# SUBBOARD-voltage_sensors.net
KiCad netlist of a schematic drawn in Altium Designer
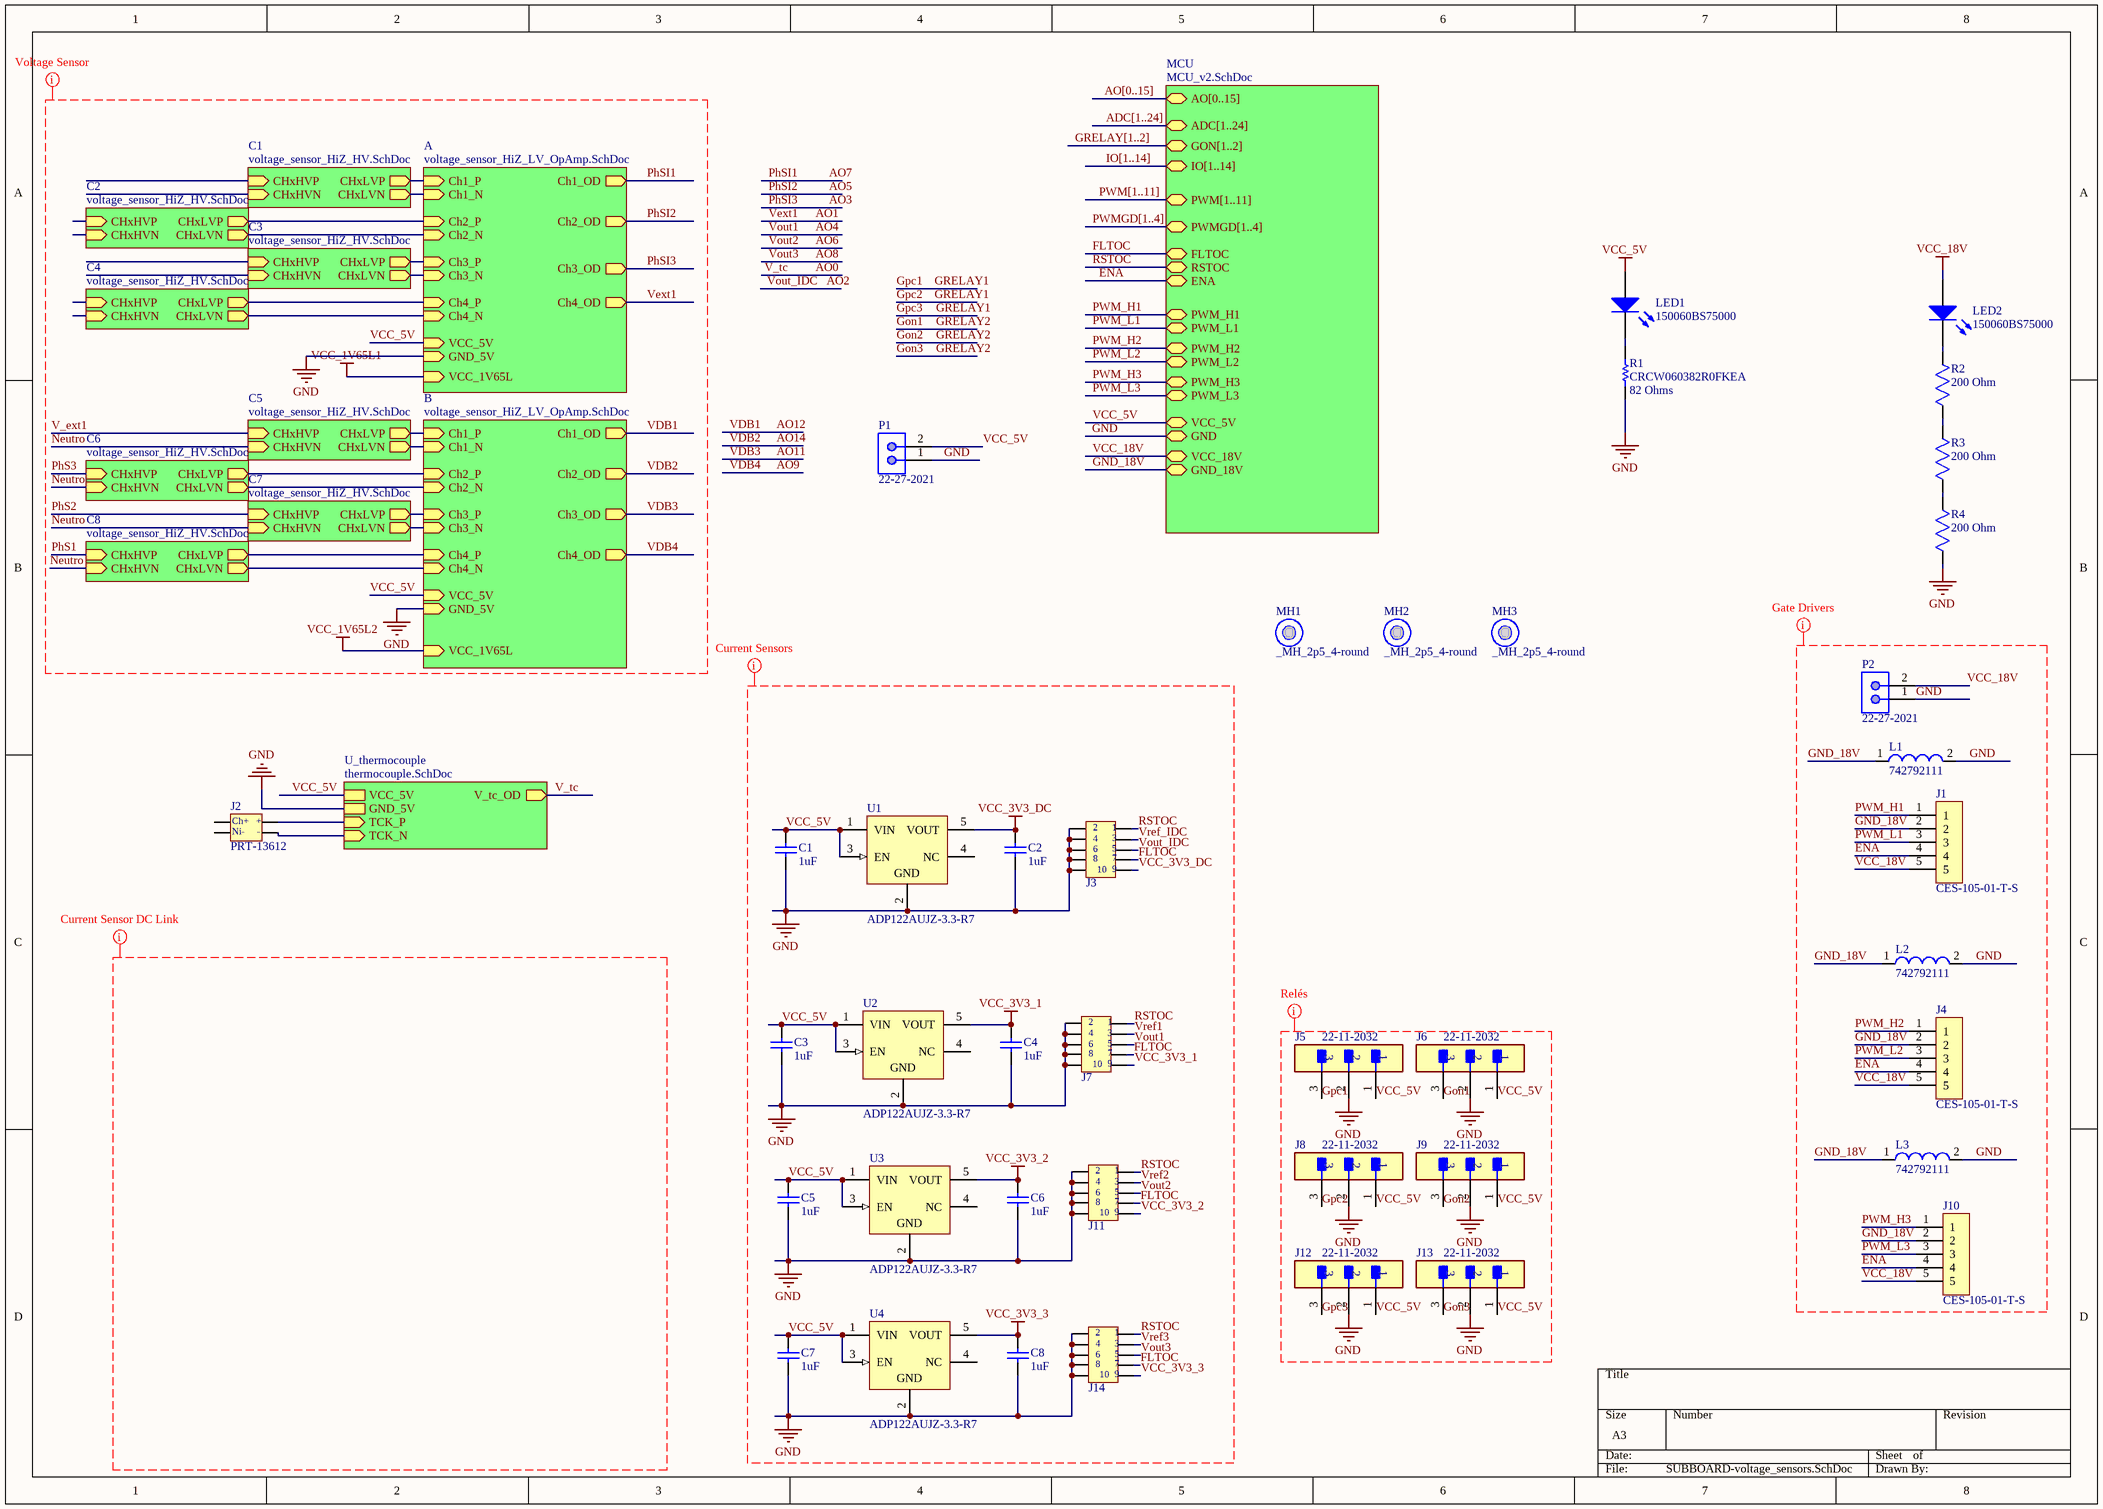
[diagram p0: SUBBOARD-voltage_sensors.SchDoc]

(export (version "E")
  (design (tool "Eeschema 10.0.6"))
  (components
    (comp (ref "C1")
      (value "1uF")
      (footprint "CAPC0603(1608)100_N")
      (description "CAP 1uF 50V ±20% 0603 (1608 Metric) Thickness 1mm SMD")
      (fields (field (name "TOLERANCE") "Â±20%") (field (name "Comment") "CAP 1uF 50V 0603(1608)"))
      (libsource (lib "Altium Content Vault") (part "CAP"))
    )
    (comp (ref "C2")
      (value "1uF")
      (footprint "CAPC0603(1608)100_N")
      (description "CAP 1uF 50V ±20% 0603 (1608 Metric) Thickness 1mm SMD")
      (fields (field (name "TOLERANCE") "Â±20%") (field (name "Comment") "CAP 1uF 50V 0603(1608)"))
      (libsource (lib "Altium Content Vault") (part "CAP"))
    )
    (comp (ref "C3")
      (value "1uF")
      (footprint "CAPC0603(1608)100_N")
      (description "CAP 1uF 50V ±20% 0603 (1608 Metric) Thickness 1mm SMD")
      (fields (field (name "TOLERANCE") "Â±20%") (field (name "Comment") "CAP 1uF 50V 0603(1608)"))
      (libsource (lib "Altium Content Vault") (part "CAP"))
    )
    (comp (ref "C4")
      (value "1uF")
      (footprint "CAPC0603(1608)100_N")
      (description "CAP 1uF 50V ±20% 0603 (1608 Metric) Thickness 1mm SMD")
      (fields (field (name "TOLERANCE") "Â±20%") (field (name "Comment") "CAP 1uF 50V 0603(1608)"))
      (libsource (lib "Altium Content Vault") (part "CAP"))
    )
    (comp (ref "C5")
      (value "1uF")
      (footprint "CAPC0603(1608)100_N")
      (description "CAP 1uF 50V ±20% 0603 (1608 Metric) Thickness 1mm SMD")
      (fields (field (name "TOLERANCE") "Â±20%") (field (name "Comment") "CAP 1uF 50V 0603(1608)"))
      (libsource (lib "Altium Content Vault") (part "CAP"))
    )
    (comp (ref "C6")
      (value "1uF")
      (footprint "CAPC0603(1608)100_N")
      (description "CAP 1uF 50V ±20% 0603 (1608 Metric) Thickness 1mm SMD")
      (fields (field (name "TOLERANCE") "Â±20%") (field (name "Comment") "CAP 1uF 50V 0603(1608)"))
      (libsource (lib "Altium Content Vault") (part "CAP"))
    )
    (comp (ref "C7")
      (value "1uF")
      (footprint "CAPC0603(1608)100_N")
      (description "CAP 1uF 50V ±20% 0603 (1608 Metric) Thickness 1mm SMD")
      (fields (field (name "TOLERANCE") "Â±20%") (field (name "Comment") "CAP 1uF 50V 0603(1608)"))
      (libsource (lib "Altium Content Vault") (part "CAP"))
    )
    (comp (ref "C8")
      (value "1uF")
      (footprint "CAPC0603(1608)100_N")
      (description "CAP 1uF 50V ±20% 0603 (1608 Metric) Thickness 1mm SMD")
      (fields (field (name "TOLERANCE") "Â±20%") (field (name "Comment") "CAP 1uF 50V 0603(1608)"))
      (libsource (lib "Altium Content Vault") (part "CAP"))
    )
    (comp (ref "J1")
      (value "CES-105-01-T-S")
      (footprint "CES-105-01-T-S")
      (fields (field (name "MANUFACTURER") "Samtec"))
      (libsource (lib "Altium_Library_POWERLAB") (part "CES-105-01-T-S"))
    )
    (comp (ref "J2")
      (value "PRT-13612")
      (footprint "PRT-13612")
      (description "THERMOCOUPLE CONN - PCC-SMP-K")
      (fields (field (name "MANUFACTURER") "SparkFun"))
      (libsource (lib "Altium_Library_POWERLAB") (part "PRT-13612"))
    )
    (comp (ref "J3")
      (value "0878311020")
      (footprint "0878311020")
      (description "Conn Shrouded Header HDR 10 POS 2mm Solder ST Thru-Hole Milli-Grid™ Tube")
      (fields (field (name "MANUFACTURER") "Molex"))
      (libsource (lib "Altium_Library_POWERLAB") (part "0878311020"))
    )
    (comp (ref "J4")
      (value "CES-105-01-T-S")
      (footprint "CES-105-01-T-S")
      (fields (field (name "MANUFACTURER") "Samtec"))
      (libsource (lib "Altium_Library_POWERLAB") (part "CES-105-01-T-S"))
    )
    (comp (ref "J5")
      (value "22-11-2032")
      (footprint "FP-22-11-2032-MFG")
      (description "CONN HEADER VERT 3POS 2.54MM")
      (fields
        (field (name "MANUFACTURER") "Molex")
        (field (name "OCTOPART") "https://octopart.com/22-11-2032-molex-10085")
      )
      (libsource (lib "Altium Content Vault") (part "0d3f023dd272f625e17a2be33dea85f"))
    )
    (comp (ref "J6")
      (value "22-11-2032")
      (footprint "FP-22-11-2032-MFG")
      (description "CONN HEADER VERT 3POS 2.54MM")
      (fields
        (field (name "MANUFACTURER") "Molex")
        (field (name "OCTOPART") "https://octopart.com/22-11-2032-molex-10085")
      )
      (libsource (lib "Altium Content Vault") (part "0d3f023dd272f625e17a2be33dea85f"))
    )
    (comp (ref "J7")
      (value "0878311020")
      (footprint "0878311020")
      (description "Conn Shrouded Header HDR 10 POS 2mm Solder ST Thru-Hole Milli-Grid™ Tube")
      (fields (field (name "MANUFACTURER") "Molex"))
      (libsource (lib "Altium_Library_POWERLAB") (part "0878311020"))
    )
    (comp (ref "J8")
      (value "22-11-2032")
      (footprint "FP-22-11-2032-MFG")
      (description "CONN HEADER VERT 3POS 2.54MM")
      (fields
        (field (name "MANUFACTURER") "Molex")
        (field (name "OCTOPART") "https://octopart.com/22-11-2032-molex-10085")
      )
      (libsource (lib "Altium Content Vault") (part "0d3f023dd272f625e17a2be33dea85f"))
    )
    (comp (ref "J9")
      (value "22-11-2032")
      (footprint "FP-22-11-2032-MFG")
      (description "CONN HEADER VERT 3POS 2.54MM")
      (fields
        (field (name "MANUFACTURER") "Molex")
        (field (name "OCTOPART") "https://octopart.com/22-11-2032-molex-10085")
      )
      (libsource (lib "Altium Content Vault") (part "0d3f023dd272f625e17a2be33dea85f"))
    )
    (comp (ref "J10")
      (value "CES-105-01-T-S")
      (footprint "CES-105-01-T-S")
      (fields (field (name "MANUFACTURER") "Samtec"))
      (libsource (lib "Altium_Library_POWERLAB") (part "CES-105-01-T-S"))
    )
    (comp (ref "J11")
      (value "0878311020")
      (footprint "0878311020")
      (description "Conn Shrouded Header HDR 10 POS 2mm Solder ST Thru-Hole Milli-Grid™ Tube")
      (fields (field (name "MANUFACTURER") "Molex"))
      (libsource (lib "Altium_Library_POWERLAB") (part "0878311020"))
    )
    (comp (ref "J12")
      (value "22-11-2032")
      (footprint "FP-22-11-2032-MFG")
      (description "CONN HEADER VERT 3POS 2.54MM")
      (fields
        (field (name "MANUFACTURER") "Molex")
        (field (name "OCTOPART") "https://octopart.com/22-11-2032-molex-10085")
      )
      (libsource (lib "Altium Content Vault") (part "0d3f023dd272f625e17a2be33dea85f"))
    )
    (comp (ref "J13")
      (value "22-11-2032")
      (footprint "FP-22-11-2032-MFG")
      (description "CONN HEADER VERT 3POS 2.54MM")
      (fields
        (field (name "MANUFACTURER") "Molex")
        (field (name "OCTOPART") "https://octopart.com/22-11-2032-molex-10085")
      )
      (libsource (lib "Altium Content Vault") (part "0d3f023dd272f625e17a2be33dea85f"))
    )
    (comp (ref "J14")
      (value "0878311020")
      (footprint "0878311020")
      (description "Conn Shrouded Header HDR 10 POS 2mm Solder ST Thru-Hole Milli-Grid™ Tube")
      (fields (field (name "MANUFACTURER") "Molex"))
      (libsource (lib "Altium_Library_POWERLAB") (part "0878311020"))
    )
    (comp (ref "L1")
      (value "742792111")
      (footprint "SMD-1206")
      (description "SMD EMI Suppression Ferrite Bead WE-CBF, Z = 26 Ohm")
      (libsource (lib "Altium Content Vault") (part "PAS-IND-INDUCTOR-2"))
    )
    (comp (ref "L2")
      (value "742792111")
      (footprint "SMD-1206")
      (description "SMD EMI Suppression Ferrite Bead WE-CBF, Z = 26 Ohm")
      (libsource (lib "Altium Content Vault") (part "PAS-IND-INDUCTOR-2"))
    )
    (comp (ref "L3")
      (value "742792111")
      (footprint "SMD-1206")
      (description "SMD EMI Suppression Ferrite Bead WE-CBF, Z = 26 Ohm")
      (libsource (lib "Altium Content Vault") (part "PAS-IND-INDUCTOR-2"))
    )
    (comp (ref "LED1")
      (value "150060BS75000")
      (footprint "0603_A")
      (description "SMD mono-color Chip LED, WL-SMCW, Blue")
      (fields (field (name "MANUFACTURER") "Wuerth Elektronik"))
      (libsource (lib "Altium Content Vault") (part "WE-LED_K1A2-2"))
    )
    (comp (ref "LED2")
      (value "150060BS75000")
      (footprint "0603_A")
      (description "SMD mono-color Chip LED, WL-SMCW, Blue")
      (fields (field (name "MANUFACTURER") "Wuerth Elektronik"))
      (libsource (lib "Altium Content Vault") (part "WE-LED_K1A2-2"))
    )
    (comp (ref "MH1")
      (value "_MH_2p5_4-round")
      (footprint "_MH_2p5_4-round")
      (description "matching hole 2.5 hole, 4mm pad (round)")
      (libsource (lib "Altium_Library_POWERLAB") (part "_MH_2p5_4-round"))
    )
    (comp (ref "MH2")
      (value "_MH_2p5_4-round")
      (footprint "_MH_2p5_4-round")
      (description "matching hole 2.5 hole, 4mm pad (round)")
      (libsource (lib "Altium_Library_POWERLAB") (part "_MH_2p5_4-round"))
    )
    (comp (ref "MH3")
      (value "_MH_2p5_4-round")
      (footprint "_MH_2p5_4-round")
      (description "matching hole 2.5 hole, 4mm pad (round)")
      (libsource (lib "Altium_Library_POWERLAB") (part "_MH_2p5_4-round"))
    )
    (comp (ref "P1")
      (value "22-27-2021")
      (footprint "MOLX-22-27-2021_V")
      (fields (field (name "MANUFACTURER") "Molex") (field (name "PARTNUMBER") "0022272021"))
      (libsource (lib "Altium Content Vault") (part "CN-1P-M-R2"))
    )
    (comp (ref "P2")
      (value "22-27-2021")
      (footprint "MOLX-22-27-2021_V")
      (fields (field (name "MANUFACTURER") "Molex") (field (name "PARTNUMBER") "0022272021"))
      (libsource (lib "Altium Content Vault") (part "CN-1P-M-R2"))
    )
    (comp (ref "R1")
      (value "CRCW060382R0FKEA")
      (footprint "RESC1609X50X30LL10T20")
      (fields (field (name "MANUFACTURER") "Vishay Dale") (field (name "ALTIUM_VALUE") "82 Ohms"))
      (libsource (lib "Altium Content Vault") (part "RES"))
    )
    (comp (ref "R2")
      (value "200 Ohm")
      (footprint "CRCW0603200RFKEAHP")
      (description "CRCW0603200RFKEAHP\r\nRes Thick Film 0603 200 Ohm 1% 0.25W(1/4W) ±100ppm/C Pad SMD Automotive T/R")
      (fields
        (field (name "MANUFACTURER") "Vishay Dale")
        (field (name "MANUFACTURER PART NUMBER") "CRCW0603200RFKEAHP")
      )
      (libsource (lib "Altium_Library_POWERLAB") (part "CRCW0603200RFKEAHP"))
    )
    (comp (ref "R3")
      (value "200 Ohm")
      (footprint "CRCW0603200RFKEAHP")
      (description "CRCW0603200RFKEAHP\r\nRes Thick Film 0603 200 Ohm 1% 0.25W(1/4W) ±100ppm/C Pad SMD Automotive T/R")
      (fields
        (field (name "MANUFACTURER") "Vishay Dale")
        (field (name "MANUFACTURER PART NUMBER") "CRCW0603200RFKEAHP")
      )
      (libsource (lib "Altium_Library_POWERLAB") (part "CRCW0603200RFKEAHP"))
    )
    (comp (ref "R4")
      (value "200 Ohm")
      (footprint "CRCW0603200RFKEAHP")
      (description "CRCW0603200RFKEAHP\r\nRes Thick Film 0603 200 Ohm 1% 0.25W(1/4W) ±100ppm/C Pad SMD Automotive T/R")
      (fields
        (field (name "MANUFACTURER") "Vishay Dale")
        (field (name "MANUFACTURER PART NUMBER") "CRCW0603200RFKEAHP")
      )
      (libsource (lib "Altium_Library_POWERLAB") (part "CRCW0603200RFKEAHP"))
    )
    (comp (ref "U1")
      (value "ADP122AUJZ-3.3-R7")
      (footprint "ADI-UJ-5_N")
      (fields (field (name "MANUFACTURER") "Analog Devices"))
      (libsource (lib "Altium Content Vault") (part "ADI-ADP1XX-UJ-5"))
    )
    (comp (ref "U2")
      (value "ADP122AUJZ-3.3-R7")
      (footprint "ADI-UJ-5_N")
      (fields (field (name "MANUFACTURER") "Analog Devices"))
      (libsource (lib "Altium Content Vault") (part "ADI-ADP1XX-UJ-5"))
    )
    (comp (ref "U3")
      (value "ADP122AUJZ-3.3-R7")
      (footprint "ADI-UJ-5_N")
      (fields (field (name "MANUFACTURER") "Analog Devices"))
      (libsource (lib "Altium Content Vault") (part "ADI-ADP1XX-UJ-5"))
    )
    (comp (ref "U4")
      (value "ADP122AUJZ-3.3-R7")
      (footprint "ADI-UJ-5_N")
      (fields (field (name "MANUFACTURER") "Analog Devices"))
      (libsource (lib "Altium Content Vault") (part "ADI-ADP1XX-UJ-5"))
    )
  )
  (nets
    (net (code "60") (name "/AO2") (class "Default")
      (node (ref "J3") (pin "5") (pinfunction "5_5") (pintype "passive"))
    )
    (net (code "62") (name "/AO4") (class "Default")
      (node (ref "J7") (pin "5") (pinfunction "5_5") (pintype "passive"))
    )
    (net (code "64") (name "/AO6") (class "Default")
      (node (ref "J11") (pin "5") (pinfunction "5_5") (pintype "passive"))
    )
    (net (code "66") (name "/AO8") (class "Default")
      (node (ref "J14") (pin "5") (pinfunction "5_5") (pintype "passive"))
    )
    (net (code "96") (name "/ENA") (class "Default")
      (node (ref "J1") (pin "4") (pinfunction "4_4") (pintype "passive"))
      (node (ref "J10") (pin "4") (pinfunction "4_4") (pintype "passive"))
      (node (ref "J4") (pin "4") (pinfunction "4_4") (pintype "passive"))
    )
    (net (code "97") (name "/FLTOC") (class "Default")
      (node (ref "J11") (pin "7") (pinfunction "7_7") (pintype "passive"))
      (node (ref "J14") (pin "7") (pinfunction "7_7") (pintype "passive"))
      (node (ref "J3") (pin "7") (pinfunction "7_7") (pintype "passive"))
      (node (ref "J7") (pin "7") (pinfunction "7_7") (pintype "passive"))
    )
    (net (code "98") (name "/GND_18V") (class "Default")
      (node (ref "J1") (pin "2") (pinfunction "2_2") (pintype "passive"))
      (node (ref "J10") (pin "2") (pinfunction "2_2") (pintype "passive"))
      (node (ref "J4") (pin "2") (pinfunction "2_2") (pintype "passive"))
      (node (ref "L1") (pin "1") (pinfunction "1_1") (pintype "passive"))
      (node (ref "L2") (pin "1") (pinfunction "1_1") (pintype "passive"))
      (node (ref "L3") (pin "1") (pinfunction "1_1") (pintype "passive"))
    )
    (net (code "99") (name "/GRELAY1") (class "Default")
      (node (ref "J12") (pin "3") (pinfunction "3_3") (pintype "passive"))
      (node (ref "J5") (pin "3") (pinfunction "3_3") (pintype "passive"))
      (node (ref "J8") (pin "3") (pinfunction "3_3") (pintype "passive"))
    )
    (net (code "100") (name "/GRELAY2") (class "Default")
      (node (ref "J13") (pin "3") (pinfunction "3_3") (pintype "passive"))
      (node (ref "J6") (pin "3") (pinfunction "3_3") (pintype "passive"))
      (node (ref "J9") (pin "3") (pinfunction "3_3") (pintype "passive"))
    )
    (net (code "106") (name "/PWM_H1") (class "Default")
      (node (ref "J1") (pin "1") (pinfunction "1_1") (pintype "passive"))
    )
    (net (code "107") (name "/PWM_H2") (class "Default")
      (node (ref "J4") (pin "1") (pinfunction "1_1") (pintype "passive"))
    )
    (net (code "108") (name "/PWM_H3") (class "Default")
      (node (ref "J10") (pin "1") (pinfunction "1_1") (pintype "passive"))
    )
    (net (code "109") (name "/PWM_L1") (class "Default")
      (node (ref "J1") (pin "3") (pinfunction "3_3") (pintype "passive"))
    )
    (net (code "110") (name "/PWM_L2") (class "Default")
      (node (ref "J4") (pin "3") (pinfunction "3_3") (pintype "passive"))
    )
    (net (code "111") (name "/PWM_L3") (class "Default")
      (node (ref "J10") (pin "3") (pinfunction "3_3") (pintype "passive"))
    )
    (net (code "115") (name "/RSTOC") (class "Default")
      (node (ref "J11") (pin "1") (pinfunction "1_1") (pintype "passive"))
      (node (ref "J14") (pin "1") (pinfunction "1_1") (pintype "passive"))
      (node (ref "J3") (pin "1") (pinfunction "1_1") (pintype "passive"))
      (node (ref "J7") (pin "1") (pinfunction "1_1") (pintype "passive"))
    )
    (net (code "116") (name "/TCK_N") (class "Default")
      (node (ref "J2") (pin "4") (pinfunction "4_4") (pintype "passive"))
    )
    (net (code "117") (name "/TCK_P") (class "Default")
      (node (ref "J2") (pin "3") (pinfunction "3_3") (pintype "passive"))
    )
    (net (code "119") (name "/Vref1") (class "Default")
      (node (ref "J7") (pin "3") (pinfunction "3_3") (pintype "passive"))
    )
    (net (code "120") (name "/Vref2") (class "Default")
      (node (ref "J11") (pin "3") (pinfunction "3_3") (pintype "passive"))
    )
    (net (code "121") (name "/Vref3") (class "Default")
      (node (ref "J14") (pin "3") (pinfunction "3_3") (pintype "passive"))
    )
    (net (code "122") (name "/Vref_IDC") (class "Default")
      (node (ref "J3") (pin "3") (pinfunction "3_3") (pintype "passive"))
    )
    (net (code "123") (name "GND") (class "Default")
      (node (ref "C1") (pin "1") (pinfunction "1_1") (pintype "passive"))
      (node (ref "C2") (pin "1") (pinfunction "1_1") (pintype "passive"))
      (node (ref "C3") (pin "1") (pinfunction "1_1") (pintype "passive"))
      (node (ref "C4") (pin "1") (pinfunction "1_1") (pintype "passive"))
      (node (ref "C5") (pin "1") (pinfunction "1_1") (pintype "passive"))
      (node (ref "C6") (pin "1") (pinfunction "1_1") (pintype "passive"))
      (node (ref "C7") (pin "1") (pinfunction "1_1") (pintype "passive"))
      (node (ref "C8") (pin "1") (pinfunction "1_1") (pintype "passive"))
      (node (ref "J11") (pin "10") (pinfunction "10_10") (pintype "passive"))
      (node (ref "J11") (pin "2") (pinfunction "2_2") (pintype "passive"))
      (node (ref "J11") (pin "4") (pinfunction "4_4") (pintype "passive"))
      (node (ref "J11") (pin "6") (pinfunction "6_6") (pintype "passive"))
      (node (ref "J11") (pin "8") (pinfunction "8_8") (pintype "passive"))
      (node (ref "J12") (pin "2") (pinfunction "2_2") (pintype "passive"))
      (node (ref "J13") (pin "2") (pinfunction "2_2") (pintype "passive"))
      (node (ref "J14") (pin "10") (pinfunction "10_10") (pintype "passive"))
      (node (ref "J14") (pin "2") (pinfunction "2_2") (pintype "passive"))
      (node (ref "J14") (pin "4") (pinfunction "4_4") (pintype "passive"))
      (node (ref "J14") (pin "6") (pinfunction "6_6") (pintype "passive"))
      (node (ref "J14") (pin "8") (pinfunction "8_8") (pintype "passive"))
      (node (ref "J3") (pin "10") (pinfunction "10_10") (pintype "passive"))
      (node (ref "J3") (pin "2") (pinfunction "2_2") (pintype "passive"))
      (node (ref "J3") (pin "4") (pinfunction "4_4") (pintype "passive"))
      (node (ref "J3") (pin "6") (pinfunction "6_6") (pintype "passive"))
      (node (ref "J3") (pin "8") (pinfunction "8_8") (pintype "passive"))
      (node (ref "J5") (pin "2") (pinfunction "2_2") (pintype "passive"))
      (node (ref "J6") (pin "2") (pinfunction "2_2") (pintype "passive"))
      (node (ref "J7") (pin "10") (pinfunction "10_10") (pintype "passive"))
      (node (ref "J7") (pin "2") (pinfunction "2_2") (pintype "passive"))
      (node (ref "J7") (pin "4") (pinfunction "4_4") (pintype "passive"))
      (node (ref "J7") (pin "6") (pinfunction "6_6") (pintype "passive"))
      (node (ref "J7") (pin "8") (pinfunction "8_8") (pintype "passive"))
      (node (ref "J8") (pin "2") (pinfunction "2_2") (pintype "passive"))
      (node (ref "J9") (pin "2") (pinfunction "2_2") (pintype "passive"))
      (node (ref "L1") (pin "2") (pinfunction "2_2") (pintype "passive"))
      (node (ref "L2") (pin "2") (pinfunction "2_2") (pintype "passive"))
      (node (ref "L3") (pin "2") (pinfunction "2_2") (pintype "passive"))
      (node (ref "P1") (pin "1") (pinfunction "1_1") (pintype "passive"))
      (node (ref "P2") (pin "1") (pinfunction "1_1") (pintype "passive"))
      (node (ref "R1") (pin "2") (pinfunction "2_2") (pintype "passive"))
      (node (ref "R4") (pin "1") (pinfunction "1_1") (pintype "passive"))
      (node (ref "U1") (pin "2") (pinfunction "GND_2") (pintype "power_in"))
      (node (ref "U2") (pin "2") (pinfunction "GND_2") (pintype "power_in"))
      (node (ref "U3") (pin "2") (pinfunction "GND_2") (pintype "power_in"))
      (node (ref "U4") (pin "2") (pinfunction "GND_2") (pintype "power_in"))
    )
    (net (code "124") (name "Net-(LED1-K)") (class "Default")
      (node (ref "LED1") (pin "1") (pinfunction "K_1") (pintype "passive"))
      (node (ref "R1") (pin "1") (pinfunction "1_1") (pintype "passive"))
    )
    (net (code "125") (name "Net-(LED2-K)") (class "Default")
      (node (ref "LED2") (pin "1") (pinfunction "K_1") (pintype "passive"))
      (node (ref "R2") (pin "2") (pinfunction "2_2") (pintype "passive"))
    )
    (net (code "126") (name "Net-(R2-Pad1)") (class "Default")
      (node (ref "R2") (pin "1") (pinfunction "1_1") (pintype "passive"))
      (node (ref "R3") (pin "2") (pinfunction "2_2") (pintype "passive"))
    )
    (net (code "127") (name "Net-(R3-Pad1)") (class "Default")
      (node (ref "R3") (pin "1") (pinfunction "1_1") (pintype "passive"))
      (node (ref "R4") (pin "2") (pinfunction "2_2") (pintype "passive"))
    )
    (net (code "130") (name "VCC_3V3_1") (class "Default")
      (node (ref "C4") (pin "2") (pinfunction "2_2") (pintype "passive"))
      (node (ref "J7") (pin "9") (pinfunction "9_9") (pintype "passive"))
      (node (ref "U2") (pin "5") (pinfunction "VOUT_5") (pintype "power_in"))
    )
    (net (code "131") (name "VCC_3V3_2") (class "Default")
      (node (ref "C6") (pin "2") (pinfunction "2_2") (pintype "passive"))
      (node (ref "J11") (pin "9") (pinfunction "9_9") (pintype "passive"))
      (node (ref "U3") (pin "5") (pinfunction "VOUT_5") (pintype "power_in"))
    )
    (net (code "132") (name "VCC_3V3_3") (class "Default")
      (node (ref "C8") (pin "2") (pinfunction "2_2") (pintype "passive"))
      (node (ref "J14") (pin "9") (pinfunction "9_9") (pintype "passive"))
      (node (ref "U4") (pin "5") (pinfunction "VOUT_5") (pintype "power_in"))
    )
    (net (code "133") (name "VCC_3V3_DC") (class "Default")
      (node (ref "C2") (pin "2") (pinfunction "2_2") (pintype "passive"))
      (node (ref "J3") (pin "9") (pinfunction "9_9") (pintype "passive"))
      (node (ref "U1") (pin "5") (pinfunction "VOUT_5") (pintype "power_in"))
    )
    (net (code "134") (name "VCC_5V") (class "Default")
      (node (ref "C1") (pin "2") (pinfunction "2_2") (pintype "passive"))
      (node (ref "C3") (pin "2") (pinfunction "2_2") (pintype "passive"))
      (node (ref "C5") (pin "2") (pinfunction "2_2") (pintype "passive"))
      (node (ref "C7") (pin "2") (pinfunction "2_2") (pintype "passive"))
      (node (ref "J12") (pin "1") (pinfunction "1_1") (pintype "passive"))
      (node (ref "J13") (pin "1") (pinfunction "1_1") (pintype "passive"))
      (node (ref "J5") (pin "1") (pinfunction "1_1") (pintype "passive"))
      (node (ref "J6") (pin "1") (pinfunction "1_1") (pintype "passive"))
      (node (ref "J8") (pin "1") (pinfunction "1_1") (pintype "passive"))
      (node (ref "J9") (pin "1") (pinfunction "1_1") (pintype "passive"))
      (node (ref "LED1") (pin "2") (pinfunction "A_2") (pintype "passive"))
      (node (ref "P1") (pin "2") (pinfunction "2_2") (pintype "passive"))
      (node (ref "U1") (pin "1") (pinfunction "VIN_1") (pintype "power_in"))
      (node (ref "U1") (pin "3") (pinfunction "EN_3") (pintype "input"))
      (node (ref "U2") (pin "1") (pinfunction "VIN_1") (pintype "power_in"))
      (node (ref "U2") (pin "3") (pinfunction "EN_3") (pintype "input"))
      (node (ref "U3") (pin "1") (pinfunction "VIN_1") (pintype "power_in"))
      (node (ref "U3") (pin "3") (pinfunction "EN_3") (pintype "input"))
      (node (ref "U4") (pin "1") (pinfunction "VIN_1") (pintype "power_in"))
      (node (ref "U4") (pin "3") (pinfunction "EN_3") (pintype "input"))
    )
    (net (code "135") (name "VCC_18V") (class "Default")
      (node (ref "J1") (pin "5") (pinfunction "5_5") (pintype "passive"))
      (node (ref "J10") (pin "5") (pinfunction "5_5") (pintype "passive"))
      (node (ref "J4") (pin "5") (pinfunction "5_5") (pintype "passive"))
      (node (ref "LED2") (pin "2") (pinfunction "A_2") (pintype "passive"))
      (node (ref "P2") (pin "2") (pinfunction "2_2") (pintype "passive"))
    )
    (net (code "136") (name "unconnected-(J2-Pad1)") (class "Default")
      (node (ref "J2") (pin "1") (pinfunction "1_1") (pintype "passive"))
    )
    (net (code "137") (name "unconnected-(J2-Pad2)") (class "Default")
      (node (ref "J2") (pin "2") (pinfunction "2_2") (pintype "passive"))
    )
    (net (code "138") (name "unconnected-(U1-NC-Pad4)") (class "Default")
      (node (ref "U1") (pin "4") (pinfunction "NC_4") (pintype "passive"))
    )
    (net (code "139") (name "unconnected-(U2-NC-Pad4)") (class "Default")
      (node (ref "U2") (pin "4") (pinfunction "NC_4") (pintype "passive"))
    )
    (net (code "140") (name "unconnected-(U3-NC-Pad4)") (class "Default")
      (node (ref "U3") (pin "4") (pinfunction "NC_4") (pintype "passive"))
    )
    (net (code "141") (name "unconnected-(U4-NC-Pad4)") (class "Default")
      (node (ref "U4") (pin "4") (pinfunction "NC_4") (pintype "passive"))
    )
  )
)
